# viewer_rev2.net
KiCad netlist of a schematic drawn in EAGLE
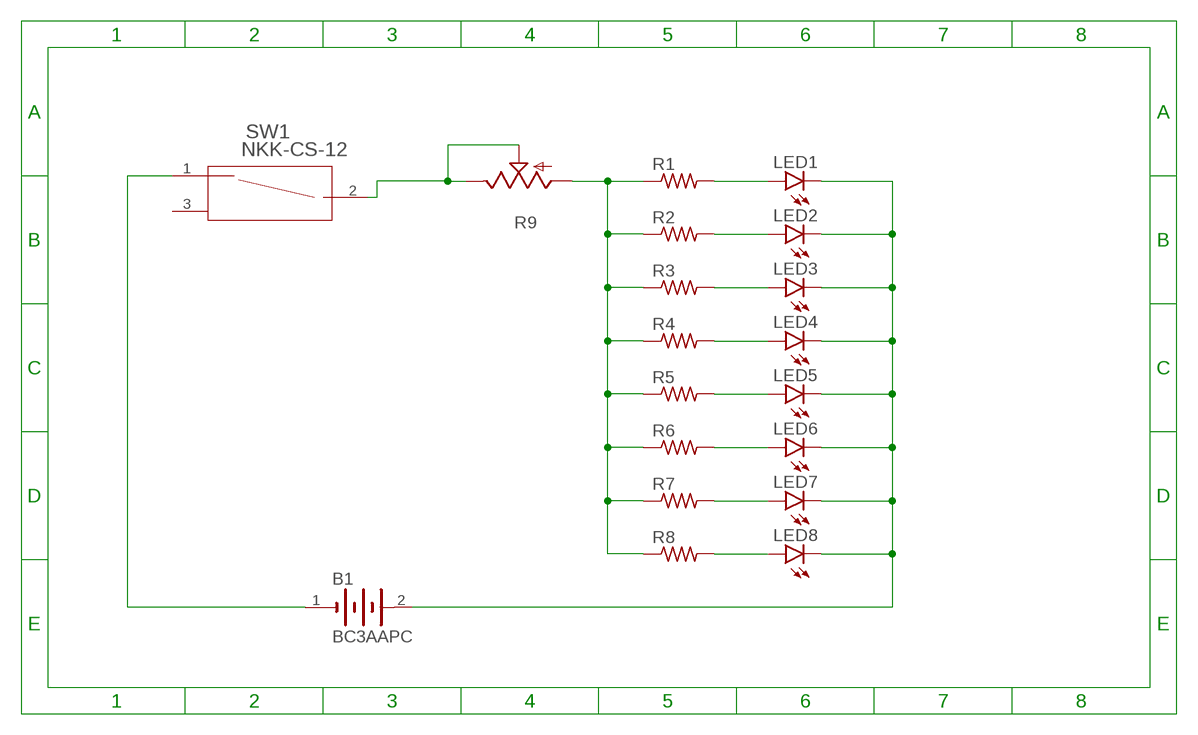
[diagram p0: schematic, sheet 1]

(export (version "E")
  (design (tool "Eeschema 10.0.6"))
  (components
    (comp (ref "B1")
      (value "BC3AAPC")
      (footprint "eagle-import:BC3AAAPC")
      (libsource (lib "eagle-import") (part "BC3AAPC"))
    )
    (comp (ref "LED1")
      (value "LED5MM")
      (footprint "eagle-import:LED5MM")
      (libsource (lib "eagle-import") (part "LED5MM"))
    )
    (comp (ref "LED2")
      (value "LED5MM")
      (footprint "eagle-import:LED5MM")
      (libsource (lib "eagle-import") (part "LED5MM"))
    )
    (comp (ref "LED3")
      (value "LED5MM")
      (footprint "eagle-import:LED5MM")
      (libsource (lib "eagle-import") (part "LED5MM"))
    )
    (comp (ref "LED4")
      (value "LED5MM")
      (footprint "eagle-import:LED5MM")
      (libsource (lib "eagle-import") (part "LED5MM"))
    )
    (comp (ref "LED5")
      (value "LED5MM")
      (footprint "eagle-import:LED5MM")
      (libsource (lib "eagle-import") (part "LED5MM"))
    )
    (comp (ref "LED6")
      (value "LED5MM")
      (footprint "eagle-import:LED5MM")
      (libsource (lib "eagle-import") (part "LED5MM"))
    )
    (comp (ref "LED7")
      (value "LED5MM")
      (footprint "eagle-import:LED5MM")
      (libsource (lib "eagle-import") (part "LED5MM"))
    )
    (comp (ref "LED8")
      (value "LED5MM")
      (footprint "eagle-import:LED5MM")
      (libsource (lib "eagle-import") (part "LED5MM"))
    )
    (comp (ref "R1")
      (value "R-US_VMTB60")
      (footprint "eagle-import:VMTB60")
      (libsource (lib "eagle-import") (part "R-US_VMTB60"))
    )
    (comp (ref "R2")
      (value "R-US_VMTB60")
      (footprint "eagle-import:VMTB60")
      (libsource (lib "eagle-import") (part "R-US_VMTB60"))
    )
    (comp (ref "R3")
      (value "R-US_VMTB60")
      (footprint "eagle-import:VMTB60")
      (libsource (lib "eagle-import") (part "R-US_VMTB60"))
    )
    (comp (ref "R4")
      (value "R-US_VMTB60")
      (footprint "eagle-import:VMTB60")
      (libsource (lib "eagle-import") (part "R-US_VMTB60"))
    )
    (comp (ref "R5")
      (value "R-US_VMTB60")
      (footprint "eagle-import:VMTB60")
      (libsource (lib "eagle-import") (part "R-US_VMTB60"))
    )
    (comp (ref "R6")
      (value "R-US_VMTB60")
      (footprint "eagle-import:VMTB60")
      (libsource (lib "eagle-import") (part "R-US_VMTB60"))
    )
    (comp (ref "R7")
      (value "R-US_VMTB60")
      (footprint "eagle-import:VMTB60")
      (libsource (lib "eagle-import") (part "R-US_VMTB60"))
    )
    (comp (ref "R8")
      (value "R-US_VMTB60")
      (footprint "eagle-import:VMTB60")
      (libsource (lib "eagle-import") (part "R-US_VMTB60"))
    )
    (comp (ref "R9")
      (value "TRIM_US-CT6")
      (footprint "eagle-import:CT6")
      (libsource (lib "eagle-import") (part "TRIM_US-CT6"))
    )
    (comp (ref "SW1")
      (value "NKK-CS-12")
      (footprint "eagle-import:SW3-SLIDE-2POL_P185")
      (libsource (lib "eagle-import") (part "NKK-CS-12"))
    )
  )
  (nets
    (net (code "1") (name "Net-(B1-+)") (class "Default")
      (node (ref "B1") (pin "2") (pinfunction "+_2") (pintype "passive"))
      (node (ref "LED1") (pin "K") (pinfunction "C_K") (pintype "passive"))
      (node (ref "LED2") (pin "K") (pinfunction "C_K") (pintype "passive"))
      (node (ref "LED3") (pin "K") (pinfunction "C_K") (pintype "passive"))
      (node (ref "LED4") (pin "K") (pinfunction "C_K") (pintype "passive"))
      (node (ref "LED5") (pin "K") (pinfunction "C_K") (pintype "passive"))
      (node (ref "LED6") (pin "K") (pinfunction "C_K") (pintype "passive"))
      (node (ref "LED7") (pin "K") (pinfunction "C_K") (pintype "passive"))
      (node (ref "LED8") (pin "K") (pinfunction "C_K") (pintype "passive"))
    )
    (net (code "2") (name "Net-(B1--)") (class "Default")
      (node (ref "B1") (pin "1") (pinfunction "-_1") (pintype "passive"))
      (node (ref "SW1") (pin "1") (pinfunction "1_1") (pintype "passive"))
    )
    (net (code "3") (name "Net-(LED1-PadA)") (class "Default")
      (node (ref "LED1") (pin "A") (pinfunction "A_A") (pintype "passive"))
      (node (ref "R1") (pin "2") (pinfunction "2_2") (pintype "passive"))
    )
    (net (code "4") (name "Net-(LED2-PadA)") (class "Default")
      (node (ref "LED2") (pin "A") (pinfunction "A_A") (pintype "passive"))
      (node (ref "R2") (pin "2") (pinfunction "2_2") (pintype "passive"))
    )
    (net (code "5") (name "Net-(LED3-PadA)") (class "Default")
      (node (ref "LED3") (pin "A") (pinfunction "A_A") (pintype "passive"))
      (node (ref "R3") (pin "2") (pinfunction "2_2") (pintype "passive"))
    )
    (net (code "6") (name "Net-(LED4-PadA)") (class "Default")
      (node (ref "LED4") (pin "A") (pinfunction "A_A") (pintype "passive"))
      (node (ref "R4") (pin "2") (pinfunction "2_2") (pintype "passive"))
    )
    (net (code "7") (name "Net-(LED5-PadA)") (class "Default")
      (node (ref "LED5") (pin "A") (pinfunction "A_A") (pintype "passive"))
      (node (ref "R5") (pin "2") (pinfunction "2_2") (pintype "passive"))
    )
    (net (code "8") (name "Net-(LED6-PadA)") (class "Default")
      (node (ref "LED6") (pin "A") (pinfunction "A_A") (pintype "passive"))
      (node (ref "R6") (pin "2") (pinfunction "2_2") (pintype "passive"))
    )
    (net (code "9") (name "Net-(LED7-PadA)") (class "Default")
      (node (ref "LED7") (pin "A") (pinfunction "A_A") (pintype "passive"))
      (node (ref "R7") (pin "2") (pinfunction "2_2") (pintype "passive"))
    )
    (net (code "10") (name "Net-(LED8-PadA)") (class "Default")
      (node (ref "LED8") (pin "A") (pinfunction "A_A") (pintype "passive"))
      (node (ref "R8") (pin "2") (pinfunction "2_2") (pintype "passive"))
    )
    (net (code "11") (name "Net-(R1-Pad1)") (class "Default")
      (node (ref "R1") (pin "1") (pinfunction "1_1") (pintype "passive"))
      (node (ref "R2") (pin "1") (pinfunction "1_1") (pintype "passive"))
      (node (ref "R3") (pin "1") (pinfunction "1_1") (pintype "passive"))
      (node (ref "R4") (pin "1") (pinfunction "1_1") (pintype "passive"))
      (node (ref "R5") (pin "1") (pinfunction "1_1") (pintype "passive"))
      (node (ref "R6") (pin "1") (pinfunction "1_1") (pintype "passive"))
      (node (ref "R7") (pin "1") (pinfunction "1_1") (pintype "passive"))
      (node (ref "R8") (pin "1") (pinfunction "1_1") (pintype "passive"))
      (node (ref "R9") (pin "A") (pinfunction "A_A") (pintype "passive"))
    )
    (net (code "12") (name "Net-(SW1-3)") (class "Default")
      (node (ref "R9") (pin "E") (pinfunction "E_E") (pintype "passive"))
      (node (ref "R9") (pin "S") (pinfunction "S_S") (pintype "passive"))
      (node (ref "SW1") (pin "2") (pinfunction "3_2") (pintype "passive"))
    )
    (net (code "13") (name "unconnected-(SW1-2-Pad3)") (class "Default")
      (node (ref "SW1") (pin "3") (pinfunction "2_3") (pintype "passive"))
    )
  )
)
